# 08_CF_INTERFACE.net
KiCad netlist of a schematic drawn in Altium Designer
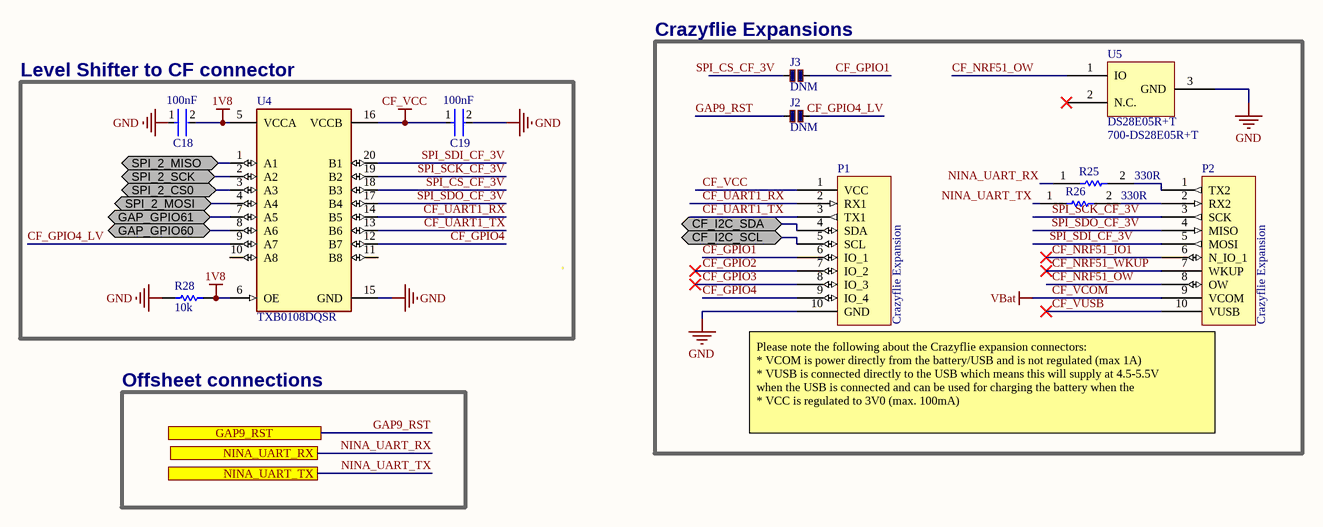
[diagram p0: 08_CF_INTERFACE.SchDoc]

(export (version "E")
  (design (tool "Eeschema 10.0.6"))
  (components
    (comp (ref "C18")
      (value "100nF")
      (footprint "FP-C1005-050-0_05-MFG")
      (description "Multilayer Ceramic Capacitors 100nF ±10% 25V X5R SMD 0402")
      (fields (field (name "TOLERANCE") "10%") (field (name "VOLTAGE") "25V"))
      (libsource (lib "Altium Content Vault") (part "b4654b650e69147ec39a6b967a45e02"))
    )
    (comp (ref "C19")
      (value "100nF")
      (footprint "FP-C1005-050-0_05-MFG")
      (description "Multilayer Ceramic Capacitors 100nF ±10% 25V X5R SMD 0402")
      (fields (field (name "TOLERANCE") "10%") (field (name "VOLTAGE") "25V"))
      (libsource (lib "Altium Content Vault") (part "b4654b650e69147ec39a6b967a45e02"))
    )
    (comp (ref "J2")
      (value "DNM")
      (footprint "Small Solder Jumper")
      (libsource (lib "ETHZ Vault") (part "Solder Jumper"))
    )
    (comp (ref "J3")
      (value "DNM")
      (footprint "Small Solder Jumper")
      (libsource (lib "ETHZ Vault") (part "Solder Jumper"))
    )
    (comp (ref "P1")
      (value "Crazyflie Expansion")
      (footprint "Crazyflie:CF2-DECK-SMD-HOLES")
      (libsource (lib "Crazyflie") (part "CF_EXP_LEFT"))
    )
    (comp (ref "P2")
      (value "Crazyflie Expansion")
      (footprint "Crazyflie:CF2-DECK-SMD-HOLES")
      (libsource (lib "Crazyflie") (part "CF_EXP_RIGHT"))
    )
    (comp (ref "R25")
      (value "330R")
      (footprint "SamacSys:H2C/H2R")
      (description "Resistor")
      (fields
        (field (name "MANUFACTURER_PART_NUMBER") "ERJ-H2RD3300X")
        (field (name "MOUSER PART NUMBER") "667-ERJ-H2RD3300X")
      )
      (libsource (lib "SamacSys") (part "ERJ-H2RD3300X"))
    )
    (comp (ref "R26")
      (value "330R")
      (footprint "SamacSys:H2C/H2R")
      (description "Resistor")
      (fields
        (field (name "MANUFACTURER_PART_NUMBER") "ERJ-H2RD3300X")
        (field (name "MOUSER PART NUMBER") "667-ERJ-H2RD3300X")
      )
      (libsource (lib "SamacSys") (part "ERJ-H2RD3300X"))
    )
    (comp (ref "R28")
      (value "10k")
      (footprint "RESC0603X28X15LL05T05")
      (fields (field (name "MANUFACTURER") "Vishay Dale") (field (name "PART NUMBER") "CRCW020110K0FNED"))
      (libsource (lib "Altium Content Vault") (part "RES"))
    )
    (comp (ref "U4")
      (value "TXB0108DQSR")
      (footprint "FP-DQS0020A-MFG")
      (description "IC TRNSLTR BIDIRECTIONAL 20USON")
      (fields
        (field (name "OCTOPART") "https://octopart.com/txb0108dqsr-texas+instruments-18562890")
        (field (name "MANUFACTURER") "Texas Instruments")
      )
      (libsource (lib "Altium Content Vault") (part "e960266df488f1119211e873c56d163"))
    )
    (comp (ref "U5")
      (value "DS28E05R+T")
      (footprint "EEPROM:SOT23-3")
      (description "EEPROM 1-Wire 112-BYTE")
      (fields (field (name "SUPPLIER PART NUMBER 1") "700-DS28E05R+T"))
      (libsource (lib "EEPROM") (part "DS28E05R+T"))
    )
  )
  (nets
    (net (code "1") (name "/CF_GPIO1") (class "Default")
      (node (ref "J3") (pin "1") (pintype "passive"))
      (node (ref "P1") (pin "6") (pinfunction "IO_1_6") (pintype "bidirectional"))
    )
    (net (code "2") (name "/CF_GPIO2") (class "Default")
      (node (ref "P1") (pin "7") (pinfunction "IO_2_7") (pintype "bidirectional+no_connect"))
    )
    (net (code "3") (name "/CF_GPIO3") (class "Default")
      (node (ref "P1") (pin "8") (pinfunction "IO_3_8") (pintype "bidirectional+no_connect"))
    )
    (net (code "4") (name "/CF_GPIO4") (class "Default")
      (node (ref "P1") (pin "9") (pinfunction "IO_4_9") (pintype "bidirectional"))
      (node (ref "U4") (pin "12") (pinfunction "B7_12") (pintype "bidirectional"))
    )
    (net (code "5") (name "/CF_GPIO4_LV") (class "Default")
      (node (ref "J2") (pin "1") (pintype "passive"))
      (node (ref "U4") (pin "9") (pinfunction "A7_9") (pintype "bidirectional"))
    )
    (net (code "6") (name "/CF_I2C_SCL") (class "Default")
      (node (ref "P1") (pin "5") (pinfunction "SCL_5") (pintype "bidirectional"))
    )
    (net (code "7") (name "/CF_I2C_SDA") (class "Default")
      (node (ref "P1") (pin "4") (pinfunction "SDA_4") (pintype "bidirectional"))
    )
    (net (code "8") (name "/CF_NRF51_IO1") (class "Default")
      (node (ref "P2") (pin "6") (pinfunction "N_IO_1_6") (pintype "bidirectional+no_connect"))
    )
    (net (code "9") (name "/CF_NRF51_OW") (class "Default")
      (node (ref "P2") (pin "8") (pinfunction "OW_8") (pintype "bidirectional"))
      (node (ref "U5") (pin "1") (pinfunction "IO_1") (pintype "passive"))
    )
    (net (code "10") (name "/CF_NRF51_WKUP") (class "Default")
      (node (ref "P2") (pin "7") (pinfunction "WKUP_7") (pintype "passive+no_connect"))
    )
    (net (code "11") (name "/CF_UART1_RX") (class "Default")
      (node (ref "P1") (pin "2") (pinfunction "RX1_2") (pintype "input"))
      (node (ref "U4") (pin "14") (pinfunction "B5_14") (pintype "bidirectional"))
    )
    (net (code "12") (name "/CF_UART1_TX") (class "Default")
      (node (ref "P1") (pin "3") (pinfunction "TX1_3") (pintype "output"))
      (node (ref "U4") (pin "13") (pinfunction "B6_13") (pintype "bidirectional"))
    )
    (net (code "13") (name "/CF_VUSB") (class "Default")
      (node (ref "P2") (pin "10") (pinfunction "VUSB_10") (pintype "power_in+no_connect"))
    )
    (net (code "14") (name "/GAP9_RST") (class "Default") (node (ref "J2") (pin "2") (pintype "passive")))
    (net (code "15") (name "/GAP_GPIO60") (class "Default")
      (node (ref "U4") (pin "8") (pinfunction "A6_8") (pintype "bidirectional"))
    )
    (net (code "16") (name "/GAP_GPIO61") (class "Default")
      (node (ref "U4") (pin "7") (pinfunction "A5_7") (pintype "bidirectional"))
    )
    (net (code "17") (name "/NINA_UART_RX") (class "Default")
      (node (ref "R25") (pin "1") (pinfunction "1_1") (pintype "passive"))
    )
    (net (code "18") (name "/NINA_UART_TX") (class "Default")
      (node (ref "R26") (pin "1") (pinfunction "1_1") (pintype "passive"))
    )
    (net (code "19") (name "/SPI_2_CS0") (class "Default")
      (node (ref "U4") (pin "3") (pinfunction "A3_3") (pintype "bidirectional"))
    )
    (net (code "20") (name "/SPI_2_MISO") (class "Default")
      (node (ref "U4") (pin "1") (pinfunction "A1_1") (pintype "bidirectional"))
    )
    (net (code "21") (name "/SPI_2_MOSI") (class "Default")
      (node (ref "U4") (pin "4") (pinfunction "A4_4") (pintype "bidirectional"))
    )
    (net (code "22") (name "/SPI_2_SCK") (class "Default")
      (node (ref "U4") (pin "2") (pinfunction "A2_2") (pintype "bidirectional"))
    )
    (net (code "23") (name "/SPI_CS_CF_3V") (class "Default")
      (node (ref "J3") (pin "2") (pintype "passive"))
      (node (ref "U4") (pin "18") (pinfunction "B3_18") (pintype "bidirectional"))
    )
    (net (code "24") (name "/SPI_SCK_CF_3V") (class "Default")
      (node (ref "P2") (pin "3") (pinfunction "SCK_3") (pintype "output"))
      (node (ref "U4") (pin "19") (pinfunction "B2_19") (pintype "bidirectional"))
    )
    (net (code "25") (name "/SPI_SDI_CF_3V") (class "Default")
      (node (ref "P2") (pin "5") (pinfunction "MOSI_5") (pintype "output"))
      (node (ref "U4") (pin "20") (pinfunction "B1_20") (pintype "bidirectional"))
    )
    (net (code "26") (name "/SPI_SDO_CF_3V") (class "Default")
      (node (ref "P2") (pin "4") (pinfunction "MISO_4") (pintype "input"))
      (node (ref "U4") (pin "17") (pinfunction "B4_17") (pintype "bidirectional"))
    )
    (net (code "27") (name "1V8") (class "Default")
      (node (ref "C18") (pin "2") (pinfunction "2_2") (pintype "passive"))
      (node (ref "R28") (pin "1") (pinfunction "1_1") (pintype "passive"))
      (node (ref "U4") (pin "5") (pinfunction "VCCA_5") (pintype "power_in"))
      (node (ref "U4") (pin "6") (pinfunction "OE_6") (pintype "input"))
    )
    (net (code "28") (name "CF_VCC") (class "Default")
      (node (ref "C19") (pin "1") (pinfunction "1_1") (pintype "passive"))
      (node (ref "P1") (pin "1") (pinfunction "VCC_1") (pintype "power_in"))
      (node (ref "U4") (pin "16") (pinfunction "VCCB_16") (pintype "power_in"))
    )
    (net (code "29") (name "GND") (class "Default")
      (node (ref "C18") (pin "1") (pinfunction "1_1") (pintype "passive"))
      (node (ref "C19") (pin "2") (pinfunction "2_2") (pintype "passive"))
      (node (ref "P1") (pin "10") (pinfunction "GND_10") (pintype "power_in"))
      (node (ref "R28") (pin "2") (pinfunction "2_2") (pintype "passive"))
      (node (ref "U4") (pin "15") (pinfunction "GND_15") (pintype "power_in"))
      (node (ref "U5") (pin "3") (pinfunction "GND_3") (pintype "passive"))
    )
    (net (code "30") (name "Net-(P2-RX2)") (class "Default")
      (node (ref "P2") (pin "2") (pinfunction "RX2_2") (pintype "input"))
      (node (ref "R26") (pin "2") (pinfunction "2_2") (pintype "passive"))
    )
    (net (code "31") (name "Net-(P2-TX2)") (class "Default")
      (node (ref "P2") (pin "1") (pinfunction "TX2_1") (pintype "output"))
      (node (ref "R25") (pin "2") (pinfunction "2_2") (pintype "passive"))
    )
    (net (code "32") (name "VBat") (class "Default")
      (node (ref "P2") (pin "9") (pinfunction "VCOM_9") (pintype "power_in"))
    )
    (net (code "33") (name "unconnected-(U4-A8-Pad10)") (class "Default")
      (node (ref "U4") (pin "10") (pinfunction "A8_10") (pintype "bidirectional"))
    )
    (net (code "34") (name "unconnected-(U4-B8-Pad11)") (class "Default")
      (node (ref "U4") (pin "11") (pinfunction "B8_11") (pintype "bidirectional"))
    )
    (net (code "35") (name "unconnected-(U5-N.C.-Pad2)") (class "Default")
      (node (ref "U5") (pin "2") (pinfunction "N.C._2") (pintype "passive+no_connect"))
    )
  )
)
